# Power_Supply_and_LEDs.net
KiCad netlist of a schematic drawn in Altium Designer
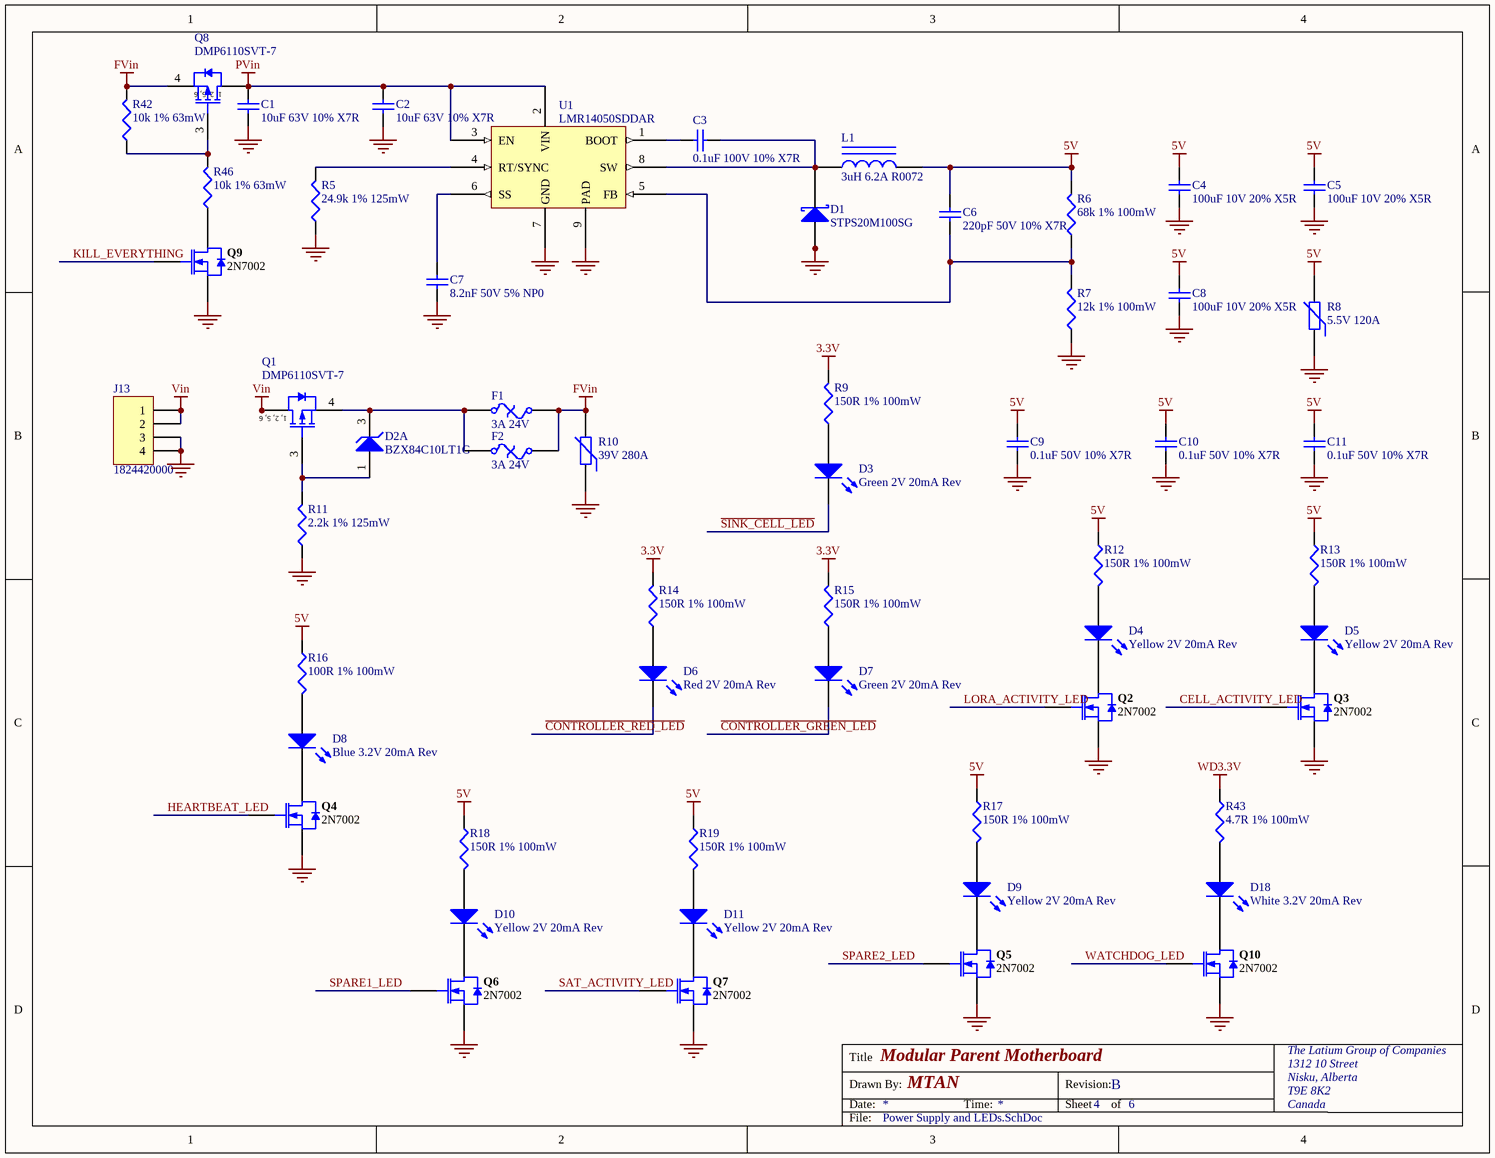
[diagram p0: Power Supply and LEDs.SchDoc]

(export (version "E")
  (design (tool "Eeschema 10.0.6"))
  (components
    (comp (ref "C1")
      (value "10uF 63V 10% X7R")
      (footprint "C1210_L")
      (description "Capacitor")
      (libsource (lib "Miscellaneous Devices") (part "Cap"))
    )
    (comp (ref "C2")
      (value "10uF 63V 10% X7R")
      (footprint "C1210_L")
      (description "Capacitor")
      (libsource (lib "Miscellaneous Devices") (part "Cap"))
    )
    (comp (ref "C3")
      (value "0.1uF 100V 10% X7R")
      (footprint "C0805")
      (description "Capacitor")
      (libsource (lib "Miscellaneous Devices") (part "Cap"))
    )
    (comp (ref "C4")
      (value "100uF 10V 20% X5R")
      (footprint "C1210_L")
      (description "Capacitor")
      (libsource (lib "Miscellaneous Devices") (part "Cap"))
    )
    (comp (ref "C5")
      (value "100uF 10V 20% X5R")
      (footprint "C1210_L")
      (description "Capacitor")
      (libsource (lib "Miscellaneous Devices") (part "Cap"))
    )
    (comp (ref "C6")
      (value "220pF 50V 10% X7R")
      (footprint "1608[0603]")
      (description "Capacitor")
      (libsource (lib "Miscellaneous Devices") (part "Cap"))
    )
    (comp (ref "C7")
      (value "8.2nF 50V 5% NP0")
      (footprint "1608[0603]")
      (description "Capacitor")
      (libsource (lib "Miscellaneous Devices") (part "Cap"))
    )
    (comp (ref "C8")
      (value "100uF 10V 20% X5R")
      (footprint "C1210_L")
      (description "Capacitor")
      (libsource (lib "Miscellaneous Devices") (part "Cap"))
    )
    (comp (ref "C9")
      (value "0.1uF 50V 10% X7R")
      (footprint "CAPC1005L")
      (description "Capacitor")
      (libsource (lib "Miscellaneous Devices") (part "Cap"))
    )
    (comp (ref "C10")
      (value "0.1uF 50V 10% X7R")
      (footprint "CAPC1005L")
      (description "Capacitor")
      (libsource (lib "Miscellaneous Devices") (part "Cap"))
    )
    (comp (ref "C11")
      (value "0.1uF 50V 10% X7R")
      (footprint "CAPC1005L")
      (description "Capacitor")
      (libsource (lib "Miscellaneous Devices") (part "Cap"))
    )
    (comp (ref "D1")
      (value "STPS20M100SG")
      (footprint "ONSC-D2PAK-3-418AJ_A_V")
      (description "DIODE SCHOTTKY 100V 20A D2PAK")
      (fields (field (name "MANUFACTURER") "STMicroelectronics"))
      (libsource (lib "Infineon Discrete Diode") (part "BAS70"))
    )
    (comp (ref "D2")
      (value "BZX84C10LT1G")
      (footprint "SOT23-3_L")
      (description "DIODE ZENER 10V 225MW SOT23-3")
      (fields (field (name "MANUFACTURER") "On Semiconductor"))
      (libsource (lib "ON Semi Zener Diodes") (part "BZX84C10LT1G"))
    )
    (comp (ref "D3")
      (value "Green 2V 20mA Rev")
      (footprint "1206 Reverse LED")
      (description "LED GRN CLEAR 2SMD BOTTOM ENTRY")
      (fields
        (field (name "MANUFACTURER") "Wurth Electronics Inc")
        (field (name "MANUFACTURER PART NUMBER") "156120VS82500")
      )
      (libsource (lib "Miscellaneous Devices") (part "LED2"))
    )
    (comp (ref "D4")
      (value "Yellow 2V 20mA Rev")
      (footprint "1206 Reverse LED")
      (description "LED YELLOW CLEAR 2SMD")
      (fields
        (field (name "MANUFACTURER") "Wurth Electronics Inc")
        (field (name "MANUFACTURER PART NUMBER") "156120YS82500")
      )
      (libsource (lib "Miscellaneous Devices") (part "LED2"))
    )
    (comp (ref "D5")
      (value "Yellow 2V 20mA Rev")
      (footprint "1206 Reverse LED")
      (description "LED YELLOW CLEAR 2SMD")
      (fields
        (field (name "MANUFACTURER") "Wurth Electronics Inc")
        (field (name "MANUFACTURER PART NUMBER") "156120YS82500")
      )
      (libsource (lib "Miscellaneous Devices") (part "LED2"))
    )
    (comp (ref "D6")
      (value "Red 2V 20mA Rev")
      (footprint "1206 Reverse LED")
      (description "LED RED CLEAR 2SMD BOTTOM ENTRY")
      (fields
        (field (name "MANUFACTURER") "Wurth Electronics Inc")
        (field (name "MANUFACTURER PART NUMBER") "156120RS82500")
      )
      (libsource (lib "Miscellaneous Devices") (part "LED2"))
    )
    (comp (ref "D7")
      (value "Green 2V 20mA Rev")
      (footprint "1206 Reverse LED")
      (description "LED GRN CLEAR 2SMD BOTTOM ENTRY")
      (fields
        (field (name "MANUFACTURER") "Wurth Electronics Inc")
        (field (name "MANUFACTURER PART NUMBER") "156120VS82500")
      )
      (libsource (lib "Miscellaneous Devices") (part "LED2"))
    )
    (comp (ref "D8")
      (value "Blue 3.2V 20mA Rev")
      (footprint "1206 Reverse LED")
      (description "LED BLUE CLEAR 2SMD BOTTOM ENTRY")
      (fields
        (field (name "MANUFACTURER") "Wurth Electronics Inc")
        (field (name "MANUFACTURER PART NUMBER") "156120BS82500")
      )
      (libsource (lib "Miscellaneous Devices") (part "LED2"))
    )
    (comp (ref "D9")
      (value "Yellow 2V 20mA Rev")
      (footprint "1206 Reverse LED")
      (description "LED YELLOW CLEAR 2SMD")
      (fields
        (field (name "MANUFACTURER") "Wurth Electronics Inc")
        (field (name "MANUFACTURER PART NUMBER") "156120YS82500")
      )
      (libsource (lib "Miscellaneous Devices") (part "LED2"))
    )
    (comp (ref "D10")
      (value "Yellow 2V 20mA Rev")
      (footprint "1206 Reverse LED")
      (description "LED YELLOW CLEAR 2SMD")
      (fields
        (field (name "MANUFACTURER") "Wurth Electronics Inc")
        (field (name "MANUFACTURER PART NUMBER") "156120YS82500")
      )
      (libsource (lib "Miscellaneous Devices") (part "LED2"))
    )
    (comp (ref "D11")
      (value "Yellow 2V 20mA Rev")
      (footprint "1206 Reverse LED")
      (description "LED YELLOW CLEAR 2SMD")
      (fields
        (field (name "MANUFACTURER") "Wurth Electronics Inc")
        (field (name "MANUFACTURER PART NUMBER") "156120YS82500")
      )
      (libsource (lib "Miscellaneous Devices") (part "LED2"))
    )
    (comp (ref "D18")
      (value "White 3.2V 20mA Rev")
      (footprint "1206 Reverse LED")
      (description "LED WHITE CLEAR 1204 SMD")
      (fields (field (name "MANUFACTURER") "Inolux") (field (name "MANUFACTURER PART NUMBER") "IN-S124BRUW"))
      (libsource (lib "Miscellaneous Devices") (part "LED2"))
    )
    (comp (ref "F1")
      (value "3A 24V")
      (footprint "2920")
      (description "Thermal Fuse")
      (fields
        (field (name "MANUFACTURER PART NUMBER") "SMDC300F/24-2")
        (field (name "MANUFACTURER") "Littelfuse Inc")
      )
      (libsource (lib "Miscellaneous Devices") (part "Fuse Thermal"))
    )
    (comp (ref "F2")
      (value "3A 24V")
      (footprint "2920")
      (description "Thermal Fuse")
      (fields
        (field (name "MANUFACTURER PART NUMBER") "SMDC300F/24-2")
        (field (name "MANUFACTURER") "Littelfuse Inc")
      )
      (libsource (lib "Miscellaneous Devices") (part "Fuse Thermal"))
    )
    (comp (ref "J13")
      (value "1824420000")
      (footprint "1824420000")
      (description "TERM BLK 2POS SIDE ENT 3.5MM PCB")
      (fields (field (name "MANUFACTURER") "Weidmuller"))
      (libsource (lib "Miscellaneous Connectors") (part "Header 4H"))
    )
    (comp (ref "L1")
      (value "3uH 6.2A R0072")
      (footprint "SRU1048")
      (description "FIXED IND 3UH 6.2A 7.2 MOHM SMD")
      (fields
        (field (name "MANUFACTURER PART NUMBER") "SRU1048-3R0Y")
        (field (name "MANUFACTURER") "Bourns Inc")
      )
      (libsource (lib "Miscellaneous Devices") (part "Inductor Iron"))
    )
    (comp (ref "Q1")
      (value "DMP6110SVT-7")
      (footprint "SOT23-6_L")
      (description "MOSFET P-CH 60V TSOT26")
      (fields (field (name "MANUFACTURER") "Diodes Incorporated"))
      (libsource (lib "ON Semi MOSFETs") (part "NTGS3136PT1G"))
    )
    (comp (ref "Q2")
      (value "2N7002")
      (footprint "INF-PG-SOT23_L")
      (description "MOSFET N-CH 60V 115MA SOT-23")
      (fields (field (name "MANUFACTURER") "ON Semiconductor"))
      (libsource (lib "Infineon Power MOSFET") (part "2N7002"))
    )
    (comp (ref "Q3")
      (value "2N7002")
      (footprint "INF-PG-SOT23_L")
      (description "MOSFET N-CH 60V 115MA SOT-23")
      (fields (field (name "MANUFACTURER") "ON Semiconductor"))
      (libsource (lib "Infineon Power MOSFET") (part "2N7002"))
    )
    (comp (ref "Q4")
      (value "2N7002")
      (footprint "INF-PG-SOT23_L")
      (description "MOSFET N-CH 60V 115MA SOT-23")
      (fields (field (name "MANUFACTURER") "ON Semiconductor"))
      (libsource (lib "Infineon Power MOSFET") (part "2N7002"))
    )
    (comp (ref "Q5")
      (value "2N7002")
      (footprint "INF-PG-SOT23_L")
      (description "MOSFET N-CH 60V 115MA SOT-23")
      (fields (field (name "MANUFACTURER") "ON Semiconductor"))
      (libsource (lib "Infineon Power MOSFET") (part "2N7002"))
    )
    (comp (ref "Q6")
      (value "2N7002")
      (footprint "INF-PG-SOT23_L")
      (description "MOSFET N-CH 60V 115MA SOT-23")
      (fields (field (name "MANUFACTURER") "ON Semiconductor"))
      (libsource (lib "Infineon Power MOSFET") (part "2N7002"))
    )
    (comp (ref "Q7")
      (value "2N7002")
      (footprint "INF-PG-SOT23_L")
      (description "MOSFET N-CH 60V 115MA SOT-23")
      (fields (field (name "MANUFACTURER") "ON Semiconductor"))
      (libsource (lib "Infineon Power MOSFET") (part "2N7002"))
    )
    (comp (ref "Q8")
      (value "DMP6110SVT-7")
      (footprint "SOT23-6_L")
      (description "MOSFET P-CH 60V TSOT26")
      (fields (field (name "MANUFACTURER") "Diodes Incorporated"))
      (libsource (lib "ON Semi MOSFETs") (part "NTGS3136PT1G"))
    )
    (comp (ref "Q9")
      (value "2N7002")
      (footprint "INF-PG-SOT23_L")
      (description "MOSFET N-CH 60V 115MA SOT-23")
      (fields (field (name "MANUFACTURER") "ON Semiconductor"))
      (libsource (lib "Infineon Power MOSFET") (part "2N7002"))
    )
    (comp (ref "Q10")
      (value "2N7002")
      (footprint "INF-PG-SOT23_L")
      (description "MOSFET N-CH 60V 115MA SOT-23")
      (fields (field (name "MANUFACTURER") "ON Semiconductor"))
      (libsource (lib "Infineon Power MOSFET") (part "2N7002"))
    )
    (comp (ref "R5")
      (value "24.9k 1% 125mW")
      (footprint "6-0805_L")
      (description "Resistor")
      (libsource (lib "Miscellaneous Devices") (part "Res3"))
    )
    (comp (ref "R6")
      (value "68k 1% 100mW")
      (footprint "J1-0603")
      (description "Resistor")
      (libsource (lib "Miscellaneous Devices") (part "Res3"))
    )
    (comp (ref "R7")
      (value "12k 1% 100mW")
      (footprint "J1-0603")
      (description "Resistor")
      (libsource (lib "Miscellaneous Devices") (part "Res3"))
    )
    (comp (ref "R8")
      (value "5.5V 120A")
      (footprint "6-0805_L")
      (description "VARISTOR 8.2V 120A 0805")
      (fields
        (field (name "MANUFACTURER") "Littelfuse Inc")
        (field (name "MANUFACTURER PART NUMBER") "V5.5MLA0805H")
      )
      (libsource (lib "Miscellaneous Devices") (part "Res Varistor"))
    )
    (comp (ref "R9")
      (value "150R 1% 100mW")
      (footprint "RESC1608L")
      (description "Resistor")
      (libsource (lib "Miscellaneous Devices") (part "Res3"))
    )
    (comp (ref "R10")
      (value "39V 280A")
      (footprint "RESC3225L")
      (description "VARISTOR 39V 280A 1210")
      (fields
        (field (name "MANUFACTURER") "Littelfuse Inc")
        (field (name "MANUFACTURER PART NUMBER") "V30MLA1210NH")
      )
      (libsource (lib "Miscellaneous Devices") (part "Res Varistor"))
    )
    (comp (ref "R11")
      (value "2.2k 1% 125mW")
      (footprint "6-0805_L")
      (description "Resistor")
      (libsource (lib "Miscellaneous Devices") (part "Res3"))
    )
    (comp (ref "R12")
      (value "150R 1% 100mW")
      (footprint "RESC1608L")
      (description "Resistor")
      (libsource (lib "Miscellaneous Devices") (part "Res3"))
    )
    (comp (ref "R13")
      (value "150R 1% 100mW")
      (footprint "RESC1608L")
      (description "Resistor")
      (libsource (lib "Miscellaneous Devices") (part "Res3"))
    )
    (comp (ref "R14")
      (value "150R 1% 100mW")
      (footprint "RESC1608L")
      (description "Resistor")
      (libsource (lib "Miscellaneous Devices") (part "Res3"))
    )
    (comp (ref "R15")
      (value "150R 1% 100mW")
      (footprint "RESC1608L")
      (description "Resistor")
      (libsource (lib "Miscellaneous Devices") (part "Res3"))
    )
    (comp (ref "R16")
      (value "100R 1% 100mW")
      (footprint "RESC1608L")
      (description "Resistor")
      (libsource (lib "Miscellaneous Devices") (part "Res3"))
    )
    (comp (ref "R17")
      (value "150R 1% 100mW")
      (footprint "RESC1608L")
      (description "Resistor")
      (libsource (lib "Miscellaneous Devices") (part "Res3"))
    )
    (comp (ref "R18")
      (value "150R 1% 100mW")
      (footprint "RESC1608L")
      (description "Resistor")
      (libsource (lib "Miscellaneous Devices") (part "Res3"))
    )
    (comp (ref "R19")
      (value "150R 1% 100mW")
      (footprint "RESC1608L")
      (description "Resistor")
      (libsource (lib "Miscellaneous Devices") (part "Res3"))
    )
    (comp (ref "R42")
      (value "10k 1% 63mW")
      (footprint "RESC1005L")
      (description "Resistor")
      (libsource (lib "Miscellaneous Devices") (part "Res3"))
    )
    (comp (ref "R43")
      (value "4.7R 1% 100mW")
      (footprint "RESC1608L")
      (description "Resistor")
      (libsource (lib "Miscellaneous Devices") (part "Res3"))
    )
    (comp (ref "R46")
      (value "10k 1% 63mW")
      (footprint "RESC1005L")
      (description "Resistor")
      (libsource (lib "Miscellaneous Devices") (part "Res3"))
    )
    (comp (ref "U1")
      (value "LMR14050SDDAR")
      (footprint "MRA08A_L")
      (description "IC REG BUCK ADJUSTABLE 5A 8SOPWR")
      (fields (field (name "MANUFACTURER") "Texas Instruments"))
      (libsource (lib "Latium Component Library") (part "LMR14050"))
    )
  )
  (nets
    (net (code "1") (name "/CELL_ACTIVITY_LED") (class "Default")
      (node (ref "Q3") (pin "1") (pinfunction "GATE_1") (pintype "passive"))
    )
    (net (code "2") (name "/HEARTBEAT_LED") (class "Default")
      (node (ref "Q4") (pin "1") (pinfunction "GATE_1") (pintype "passive"))
    )
    (net (code "3") (name "/KILL_EVERYTHING") (class "Default")
      (node (ref "Q9") (pin "1") (pinfunction "GATE_1") (pintype "passive"))
    )
    (net (code "4") (name "/LORA_ACTIVITY_LED") (class "Default")
      (node (ref "Q2") (pin "1") (pinfunction "GATE_1") (pintype "passive"))
    )
    (net (code "5") (name "/SAT_ACTIVITY_LED") (class "Default")
      (node (ref "Q7") (pin "1") (pinfunction "GATE_1") (pintype "passive"))
    )
    (net (code "6") (name "/SPARE1_LED") (class "Default")
      (node (ref "Q6") (pin "1") (pinfunction "GATE_1") (pintype "passive"))
    )
    (net (code "7") (name "/SPARE2_LED") (class "Default")
      (node (ref "Q5") (pin "1") (pinfunction "GATE_1") (pintype "passive"))
    )
    (net (code "8") (name "/WATCHDOG_LED") (class "Default")
      (node (ref "Q10") (pin "1") (pinfunction "GATE_1") (pintype "passive"))
    )
    (net (code "9") (name "/~{CONTROLLER_GREEN_LED}") (class "Default")
      (node (ref "D7") (pin "2") (pinfunction "K_2") (pintype "passive"))
    )
    (net (code "10") (name "/~{CONTROLLER_RED_LED}") (class "Default")
      (node (ref "D6") (pin "2") (pinfunction "K_2") (pintype "passive"))
    )
    (net (code "11") (name "/~{SINK_CELL_LED}") (class "Default")
      (node (ref "D3") (pin "2") (pinfunction "K_2") (pintype "passive"))
    )
    (net (code "12") (name "3.3V") (class "Default")
      (node (ref "R14") (pin "2") (pinfunction "2_2") (pintype "passive"))
      (node (ref "R15") (pin "2") (pinfunction "2_2") (pintype "passive"))
      (node (ref "R9") (pin "2") (pinfunction "2_2") (pintype "passive"))
    )
    (net (code "13") (name "5V") (class "Default")
      (node (ref "C10") (pin "1") (pinfunction "1_1") (pintype "passive"))
      (node (ref "C11") (pin "1") (pinfunction "1_1") (pintype "passive"))
      (node (ref "C4") (pin "2") (pinfunction "2_2") (pintype "passive"))
      (node (ref "C5") (pin "2") (pinfunction "2_2") (pintype "passive"))
      (node (ref "C6") (pin "2") (pinfunction "2_2") (pintype "passive"))
      (node (ref "C8") (pin "2") (pinfunction "2_2") (pintype "passive"))
      (node (ref "C9") (pin "1") (pinfunction "1_1") (pintype "passive"))
      (node (ref "L1") (pin "2") (pinfunction "2_2") (pintype "passive"))
      (node (ref "R12") (pin "1") (pinfunction "1_1") (pintype "passive"))
      (node (ref "R13") (pin "1") (pinfunction "1_1") (pintype "passive"))
      (node (ref "R16") (pin "1") (pinfunction "1_1") (pintype "passive"))
      (node (ref "R17") (pin "1") (pinfunction "1_1") (pintype "passive"))
      (node (ref "R18") (pin "1") (pinfunction "1_1") (pintype "passive"))
      (node (ref "R19") (pin "1") (pinfunction "1_1") (pintype "passive"))
      (node (ref "R6") (pin "2") (pinfunction "2_2") (pintype "passive"))
      (node (ref "R8") (pin "2") (pinfunction "2_2") (pintype "passive"))
    )
    (net (code "14") (name "FVin") (class "Default")
      (node (ref "F1") (pin "2") (pinfunction "2_2") (pintype "passive"))
      (node (ref "F2") (pin "2") (pinfunction "2_2") (pintype "passive"))
      (node (ref "Q8") (pin "4") (pinfunction "S_4") (pintype "passive"))
      (node (ref "R10") (pin "2") (pinfunction "2_2") (pintype "passive"))
      (node (ref "R42") (pin "2") (pinfunction "2_2") (pintype "passive"))
    )
    (net (code "15") (name "GND") (class "Default")
      (node (ref "C1") (pin "1") (pinfunction "1_1") (pintype "passive"))
      (node (ref "C10") (pin "2") (pinfunction "2_2") (pintype "passive"))
      (node (ref "C11") (pin "2") (pinfunction "2_2") (pintype "passive"))
      (node (ref "C2") (pin "1") (pinfunction "1_1") (pintype "passive"))
      (node (ref "C4") (pin "1") (pinfunction "1_1") (pintype "passive"))
      (node (ref "C5") (pin "1") (pinfunction "1_1") (pintype "passive"))
      (node (ref "C7") (pin "1") (pinfunction "1_1") (pintype "passive"))
      (node (ref "C8") (pin "1") (pinfunction "1_1") (pintype "passive"))
      (node (ref "C9") (pin "2") (pinfunction "2_2") (pintype "passive"))
      (node (ref "D1") (pin "1") (pinfunction "A_1") (pintype "passive"))
      (node (ref "D1") (pin "3") (pinfunction "A_3") (pintype "passive"))
      (node (ref "J13") (pin "3") (pinfunction "3_3") (pintype "passive"))
      (node (ref "J13") (pin "4") (pinfunction "4_4") (pintype "passive"))
      (node (ref "Q10") (pin "2") (pinfunction "SOURCE_2") (pintype "passive"))
      (node (ref "Q2") (pin "2") (pinfunction "SOURCE_2") (pintype "passive"))
      (node (ref "Q3") (pin "2") (pinfunction "SOURCE_2") (pintype "passive"))
      (node (ref "Q4") (pin "2") (pinfunction "SOURCE_2") (pintype "passive"))
      (node (ref "Q5") (pin "2") (pinfunction "SOURCE_2") (pintype "passive"))
      (node (ref "Q6") (pin "2") (pinfunction "SOURCE_2") (pintype "passive"))
      (node (ref "Q7") (pin "2") (pinfunction "SOURCE_2") (pintype "passive"))
      (node (ref "Q9") (pin "2") (pinfunction "SOURCE_2") (pintype "passive"))
      (node (ref "R10") (pin "1") (pinfunction "1_1") (pintype "passive"))
      (node (ref "R11") (pin "1") (pinfunction "1_1") (pintype "passive"))
      (node (ref "R5") (pin "1") (pinfunction "1_1") (pintype "passive"))
      (node (ref "R7") (pin "1") (pinfunction "1_1") (pintype "passive"))
      (node (ref "R8") (pin "1") (pinfunction "1_1") (pintype "passive"))
      (node (ref "U1") (pin "7") (pinfunction "GND_7") (pintype "power_in"))
      (node (ref "U1") (pin "9") (pinfunction "PAD_9") (pintype "power_in"))
    )
    (net (code "16") (name "Net-(D1-K)") (class "Default")
      (node (ref "C3") (pin "1") (pinfunction "1_1") (pintype "passive"))
      (node (ref "D1") (pin "4") (pinfunction "K_4") (pintype "passive"))
      (node (ref "L1") (pin "1") (pinfunction "1_1") (pintype "passive"))
      (node (ref "U1") (pin "8") (pinfunction "SW_8") (pintype "output"))
    )
    (net (code "17") (name "Net-(D2A-A)") (class "Default")
      (node (ref "D2") (pin "1") (pinfunction "A_1") (pintype "passive"))
      (node (ref "Q1") (pin "3") (pinfunction "G_3") (pintype "passive"))
      (node (ref "R11") (pin "2") (pinfunction "2_2") (pintype "passive"))
    )
    (net (code "18") (name "Net-(D2A-K)") (class "Default")
      (node (ref "D2") (pin "3") (pinfunction "K_3") (pintype "passive"))
      (node (ref "F1") (pin "1") (pinfunction "1_1") (pintype "passive"))
      (node (ref "F2") (pin "1") (pinfunction "1_1") (pintype "passive"))
      (node (ref "Q1") (pin "4") (pinfunction "S_4") (pintype "passive"))
    )
    (net (code "19") (name "Net-(D3-A)") (class "Default")
      (node (ref "D3") (pin "1") (pinfunction "A_1") (pintype "passive"))
      (node (ref "R9") (pin "1") (pinfunction "1_1") (pintype "passive"))
    )
    (net (code "20") (name "Net-(D4-A)") (class "Default")
      (node (ref "D4") (pin "1") (pinfunction "A_1") (pintype "passive"))
      (node (ref "R12") (pin "2") (pinfunction "2_2") (pintype "passive"))
    )
    (net (code "21") (name "Net-(D4-K)") (class "Default")
      (node (ref "D4") (pin "2") (pinfunction "K_2") (pintype "passive"))
      (node (ref "Q2") (pin "3") (pinfunction "DRAIN_3") (pintype "passive"))
    )
    (net (code "22") (name "Net-(D5-A)") (class "Default")
      (node (ref "D5") (pin "1") (pinfunction "A_1") (pintype "passive"))
      (node (ref "R13") (pin "2") (pinfunction "2_2") (pintype "passive"))
    )
    (net (code "23") (name "Net-(D5-K)") (class "Default")
      (node (ref "D5") (pin "2") (pinfunction "K_2") (pintype "passive"))
      (node (ref "Q3") (pin "3") (pinfunction "DRAIN_3") (pintype "passive"))
    )
    (net (code "24") (name "Net-(D6-A)") (class "Default")
      (node (ref "D6") (pin "1") (pinfunction "A_1") (pintype "passive"))
      (node (ref "R14") (pin "1") (pinfunction "1_1") (pintype "passive"))
    )
    (net (code "25") (name "Net-(D7-A)") (class "Default")
      (node (ref "D7") (pin "1") (pinfunction "A_1") (pintype "passive"))
      (node (ref "R15") (pin "1") (pinfunction "1_1") (pintype "passive"))
    )
    (net (code "26") (name "Net-(D8-A)") (class "Default")
      (node (ref "D8") (pin "1") (pinfunction "A_1") (pintype "passive"))
      (node (ref "R16") (pin "2") (pinfunction "2_2") (pintype "passive"))
    )
    (net (code "27") (name "Net-(D8-K)") (class "Default")
      (node (ref "D8") (pin "2") (pinfunction "K_2") (pintype "passive"))
      (node (ref "Q4") (pin "3") (pinfunction "DRAIN_3") (pintype "passive"))
    )
    (net (code "28") (name "Net-(D9-A)") (class "Default")
      (node (ref "D9") (pin "1") (pinfunction "A_1") (pintype "passive"))
      (node (ref "R17") (pin "2") (pinfunction "2_2") (pintype "passive"))
    )
    (net (code "29") (name "Net-(D9-K)") (class "Default")
      (node (ref "D9") (pin "2") (pinfunction "K_2") (pintype "passive"))
      (node (ref "Q5") (pin "3") (pinfunction "DRAIN_3") (pintype "passive"))
    )
    (net (code "30") (name "Net-(D10-A)") (class "Default")
      (node (ref "D10") (pin "1") (pinfunction "A_1") (pintype "passive"))
      (node (ref "R18") (pin "2") (pinfunction "2_2") (pintype "passive"))
    )
    (net (code "31") (name "Net-(D10-K)") (class "Default")
      (node (ref "D10") (pin "2") (pinfunction "K_2") (pintype "passive"))
      (node (ref "Q6") (pin "3") (pinfunction "DRAIN_3") (pintype "passive"))
    )
    (net (code "32") (name "Net-(D11-A)") (class "Default")
      (node (ref "D11") (pin "1") (pinfunction "A_1") (pintype "passive"))
      (node (ref "R19") (pin "2") (pinfunction "2_2") (pintype "passive"))
    )
    (net (code "33") (name "Net-(D11-K)") (class "Default")
      (node (ref "D11") (pin "2") (pinfunction "K_2") (pintype "passive"))
      (node (ref "Q7") (pin "3") (pinfunction "DRAIN_3") (pintype "passive"))
    )
    (net (code "34") (name "Net-(D18-A)") (class "Default")
      (node (ref "D18") (pin "1") (pinfunction "A_1") (pintype "passive"))
      (node (ref "R43") (pin "2") (pinfunction "2_2") (pintype "passive"))
    )
    (net (code "35") (name "Net-(D18-K)") (class "Default")
      (node (ref "D18") (pin "2") (pinfunction "K_2") (pintype "passive"))
      (node (ref "Q10") (pin "3") (pinfunction "DRAIN_3") (pintype "passive"))
    )
    (net (code "36") (name "Net-(Q8-G)") (class "Default")
      (node (ref "Q8") (pin "3") (pinfunction "G_3") (pintype "passive"))
      (node (ref "R42") (pin "1") (pinfunction "1_1") (pintype "passive"))
      (node (ref "R46") (pin "2") (pinfunction "2_2") (pintype "passive"))
    )
    (net (code "37") (name "Net-(Q9-DRAIN)") (class "Default")
      (node (ref "Q9") (pin "3") (pinfunction "DRAIN_3") (pintype "passive"))
      (node (ref "R46") (pin "1") (pinfunction "1_1") (pintype "passive"))
    )
    (net (code "38") (name "Net-(U1-BOOT)") (class "Default")
      (node (ref "C3") (pin "2") (pinfunction "2_2") (pintype "passive"))
      (node (ref "U1") (pin "1") (pinfunction "BOOT_1") (pintype "output"))
    )
    (net (code "39") (name "Net-(U1-FB)") (class "Default")
      (node (ref "C6") (pin "1") (pinfunction "1_1") (pintype "passive"))
      (node (ref "R6") (pin "1") (pinfunction "1_1") (pintype "passive"))
      (node (ref "R7") (pin "2") (pinfunction "2_2") (pintype "passive"))
      (node (ref "U1") (pin "5") (pinfunction "FB_5") (pintype "input"))
    )
    (net (code "40") (name "Net-(U1-RT{slash}SYNC)") (class "Default")
      (node (ref "R5") (pin "2") (pinfunction "2_2") (pintype "passive"))
      (node (ref "U1") (pin "4") (pinfunction "RT/SYNC_4") (pintype "input"))
    )
    (net (code "41") (name "Net-(U1-SS)") (class "Default")
      (node (ref "C7") (pin "2") (pinfunction "2_2") (pintype "passive"))
      (node (ref "U1") (pin "6") (pinfunction "SS_6") (pintype "output"))
    )
    (net (code "42") (name "PVin") (class "Default")
      (node (ref "C1") (pin "2") (pinfunction "2_2") (pintype "passive"))
      (node (ref "C2") (pin "2") (pinfunction "2_2") (pintype "passive"))
      (node (ref "Q8") (pin "1") (pinfunction "D_1") (pintype "passive"))
      (node (ref "Q8") (pin "2") (pinfunction "D_2") (pintype "passive"))
      (node (ref "Q8") (pin "5") (pinfunction "D_5") (pintype "passive"))
      (node (ref "Q8") (pin "6") (pinfunction "D_6") (pintype "passive"))
      (node (ref "U1") (pin "2") (pinfunction "VIN_2") (pintype "power_in"))
      (node (ref "U1") (pin "3") (pinfunction "EN_3") (pintype "input"))
    )
    (net (code "43") (name "Vin") (class "Default")
      (node (ref "J13") (pin "1") (pinfunction "1_1") (pintype "passive"))
      (node (ref "J13") (pin "2") (pinfunction "2_2") (pintype "passive"))
      (node (ref "Q1") (pin "1") (pinfunction "D_1") (pintype "passive"))
      (node (ref "Q1") (pin "2") (pinfunction "D_2") (pintype "passive"))
      (node (ref "Q1") (pin "5") (pinfunction "D_5") (pintype "passive"))
      (node (ref "Q1") (pin "6") (pinfunction "D_6") (pintype "passive"))
    )
    (net (code "44") (name "WD3.3V") (class "Default")
      (node (ref "R43") (pin "1") (pinfunction "1_1") (pintype "passive"))
    )
  )
)
